# SparkFun_ACS712LowCurrentSensorBoard.net
KiCad netlist of a schematic drawn in EAGLE
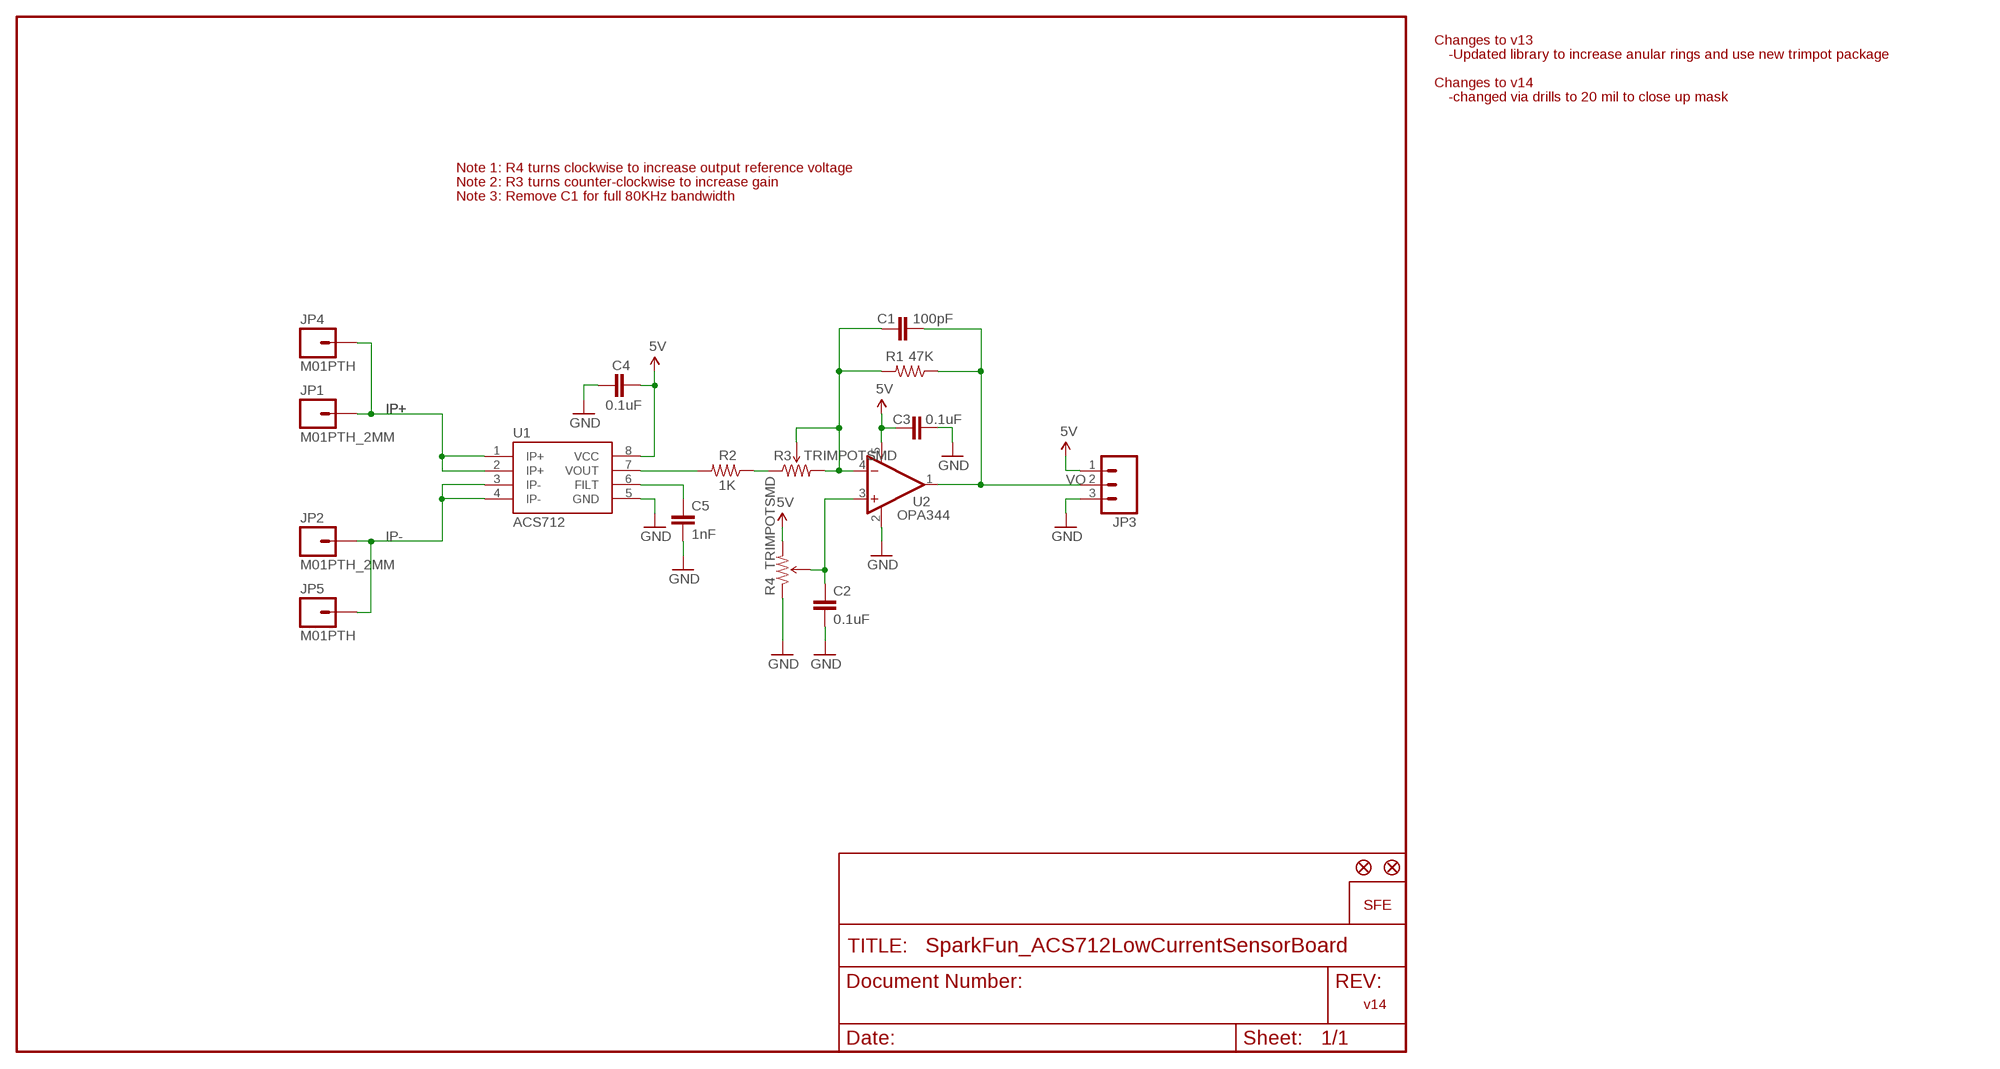
[diagram p0: schematic, sheet 1]

(export (version "E")
  (design (tool "Eeschema 10.0.6"))
  (components
    (comp (ref "C1")
      (value "100pF")
      (footprint "eagle-import:0402-CAP")
      (libsource (lib "eagle-import") (part "CAP0402-CAP"))
    )
    (comp (ref "C2")
      (value "0.1uF")
      (footprint "eagle-import:0402-CAP")
      (libsource (lib "eagle-import") (part "CAP0402-CAP"))
    )
    (comp (ref "C3")
      (value "0.1uF")
      (footprint "eagle-import:0402-CAP")
      (libsource (lib "eagle-import") (part "CAP0402-CAP"))
    )
    (comp (ref "C4")
      (value "0.1uF")
      (footprint "eagle-import:0402-CAP")
      (libsource (lib "eagle-import") (part "CAP0402-CAP"))
    )
    (comp (ref "C5")
      (value "1nF")
      (footprint "eagle-import:0402-CAP")
      (libsource (lib "eagle-import") (part "CAP0402-CAP"))
    )
    (comp (ref "JP1")
      (value "M01PTH_2MM")
      (footprint "eagle-import:1X01_2MM")
      (libsource (lib "eagle-import") (part "M01PTH_2MM"))
    )
    (comp (ref "JP2")
      (value "M01PTH_2MM")
      (footprint "eagle-import:1X01_2MM")
      (libsource (lib "eagle-import") (part "M01PTH_2MM"))
    )
    (comp (ref "JP3")
      (value "M03PTH")
      (footprint "eagle-import:1X03")
      (libsource (lib "eagle-import") (part "M03PTH"))
    )
    (comp (ref "JP4")
      (value "M01PTH")
      (footprint "eagle-import:1X01")
      (libsource (lib "eagle-import") (part "M01PTH"))
    )
    (comp (ref "JP5")
      (value "M01PTH")
      (footprint "eagle-import:1X01")
      (libsource (lib "eagle-import") (part "M01PTH"))
    )
    (comp (ref "R1")
      (value "47K")
      (footprint "eagle-import:0402-RES")
      (libsource (lib "eagle-import") (part "RESISTOR0402-RES"))
    )
    (comp (ref "R2")
      (value "1K")
      (footprint "eagle-import:0402-RES")
      (libsource (lib "eagle-import") (part "RESISTOR0402-RES"))
    )
    (comp (ref "R3")
      (value "TRIMPOTSMD")
      (footprint "eagle-import:TRIMPOT-3MM")
      (libsource (lib "eagle-import") (part "TRIMPOTSMD"))
    )
    (comp (ref "R4")
      (value "TRIMPOTSMD")
      (footprint "eagle-import:TRIMPOT-3MM")
      (libsource (lib "eagle-import") (part "TRIMPOTSMD"))
    )
    (comp (ref "U$1")
      (value "FIDUCIALUFIDUCIAL")
      (footprint "eagle-import:MICRO-FIDUCIAL")
      (libsource (lib "eagle-import") (part "FIDUCIALUFIDUCIAL"))
    )
    (comp (ref "U$2")
      (value "LOGO-SFENEW")
      (footprint "eagle-import:SFE-NEW-WEBLOGO")
      (libsource (lib "eagle-import") (part "LOGO-SFENEW"))
    )
    (comp (ref "U$3")
      (value "FIDUCIALUFIDUCIAL")
      (footprint "eagle-import:MICRO-FIDUCIAL")
      (libsource (lib "eagle-import") (part "FIDUCIALUFIDUCIAL"))
    )
    (comp (ref "U1")
      (value "ACS712")
      (footprint "eagle-import:SO08")
      (libsource (lib "eagle-import") (part "ACS712"))
    )
    (comp (ref "U2")
      (value "OPA344")
      (footprint "eagle-import:SOT23-5")
      (libsource (lib "eagle-import") (part "OPA344"))
    )
  )
  (nets
    (net (code "1") (name "/IP+") (class "Default")
      (node (ref "JP1") (pin "1") (pinfunction "1_1") (pintype "passive"))
      (node (ref "JP4") (pin "1") (pinfunction "1_1") (pintype "passive"))
      (node (ref "U1") (pin "1") (pinfunction "IP+_1") (pintype "bidirectional"))
      (node (ref "U1") (pin "2") (pinfunction "IP+_2") (pintype "bidirectional"))
    )
    (net (code "2") (name "/IP-") (class "Default")
      (node (ref "JP2") (pin "1") (pinfunction "1_1") (pintype "passive"))
      (node (ref "JP5") (pin "1") (pinfunction "1_1") (pintype "passive"))
      (node (ref "U1") (pin "3") (pinfunction "IP-_3") (pintype "bidirectional"))
      (node (ref "U1") (pin "4") (pinfunction "IP-_4") (pintype "bidirectional"))
    )
    (net (code "3") (name "/VO") (class "Default")
      (node (ref "C1") (pin "1") (pinfunction "1_1") (pintype "passive"))
      (node (ref "JP3") (pin "2") (pinfunction "2_2") (pintype "passive"))
      (node (ref "R1") (pin "1") (pinfunction "1_1") (pintype "passive"))
      (node (ref "U2") (pin "1") (pinfunction "OUT_1") (pintype "output"))
    )
    (net (code "4") (name "5V") (class "Default")
      (node (ref "C3") (pin "1") (pinfunction "1_1") (pintype "passive"))
      (node (ref "C4") (pin "2") (pinfunction "2_2") (pintype "passive"))
      (node (ref "JP3") (pin "1") (pinfunction "1_1") (pintype "passive"))
      (node (ref "R4") (pin "3") (pinfunction "CW_3") (pintype "passive"))
      (node (ref "U1") (pin "8") (pinfunction "VCC_8") (pintype "bidirectional"))
      (node (ref "U2") (pin "5") (pinfunction "V+_5") (pintype "power_in"))
    )
    (net (code "5") (name "GND") (class "Default")
      (node (ref "C2") (pin "2") (pinfunction "2_2") (pintype "passive"))
      (node (ref "C3") (pin "2") (pinfunction "2_2") (pintype "passive"))
      (node (ref "C4") (pin "1") (pinfunction "1_1") (pintype "passive"))
      (node (ref "C5") (pin "2") (pinfunction "2_2") (pintype "passive"))
      (node (ref "JP3") (pin "3") (pinfunction "3_3") (pintype "passive"))
      (node (ref "R4") (pin "1") (pinfunction "CCW_1") (pintype "passive"))
      (node (ref "U1") (pin "5") (pinfunction "GND_5") (pintype "bidirectional"))
      (node (ref "U2") (pin "2") (pinfunction "V-_2") (pintype "power_in"))
    )
    (net (code "6") (name "Net-(R3-CCW)") (class "Default")
      (node (ref "R2") (pin "1") (pinfunction "1_1") (pintype "passive"))
      (node (ref "R3") (pin "1") (pinfunction "CCW_1") (pintype "passive"))
    )
    (net (code "7") (name "Net-(R3-CW)") (class "Default")
      (node (ref "C1") (pin "2") (pinfunction "2_2") (pintype "passive"))
      (node (ref "R1") (pin "2") (pinfunction "2_2") (pintype "passive"))
      (node (ref "R3") (pin "2") (pinfunction "WIPER_2") (pintype "passive"))
      (node (ref "R3") (pin "3") (pinfunction "CW_3") (pintype "passive"))
      (node (ref "U2") (pin "4") (pinfunction "-IN_4") (pintype "input"))
    )
    (net (code "8") (name "Net-(R4-WIPER)") (class "Default")
      (node (ref "C2") (pin "1") (pinfunction "1_1") (pintype "passive"))
      (node (ref "R4") (pin "2") (pinfunction "WIPER_2") (pintype "passive"))
      (node (ref "U2") (pin "3") (pinfunction "+IN_3") (pintype "input"))
    )
    (net (code "9") (name "Net-(U1-FILT)") (class "Default")
      (node (ref "C5") (pin "1") (pinfunction "1_1") (pintype "passive"))
      (node (ref "U1") (pin "6") (pinfunction "FILT_6") (pintype "bidirectional"))
    )
    (net (code "10") (name "Net-(U1-VOUT)") (class "Default")
      (node (ref "R2") (pin "2") (pinfunction "2_2") (pintype "passive"))
      (node (ref "U1") (pin "7") (pinfunction "VOUT_7") (pintype "bidirectional"))
    )
  )
)
